# beacon.net
KiCad netlist of a schematic drawn in EAGLE
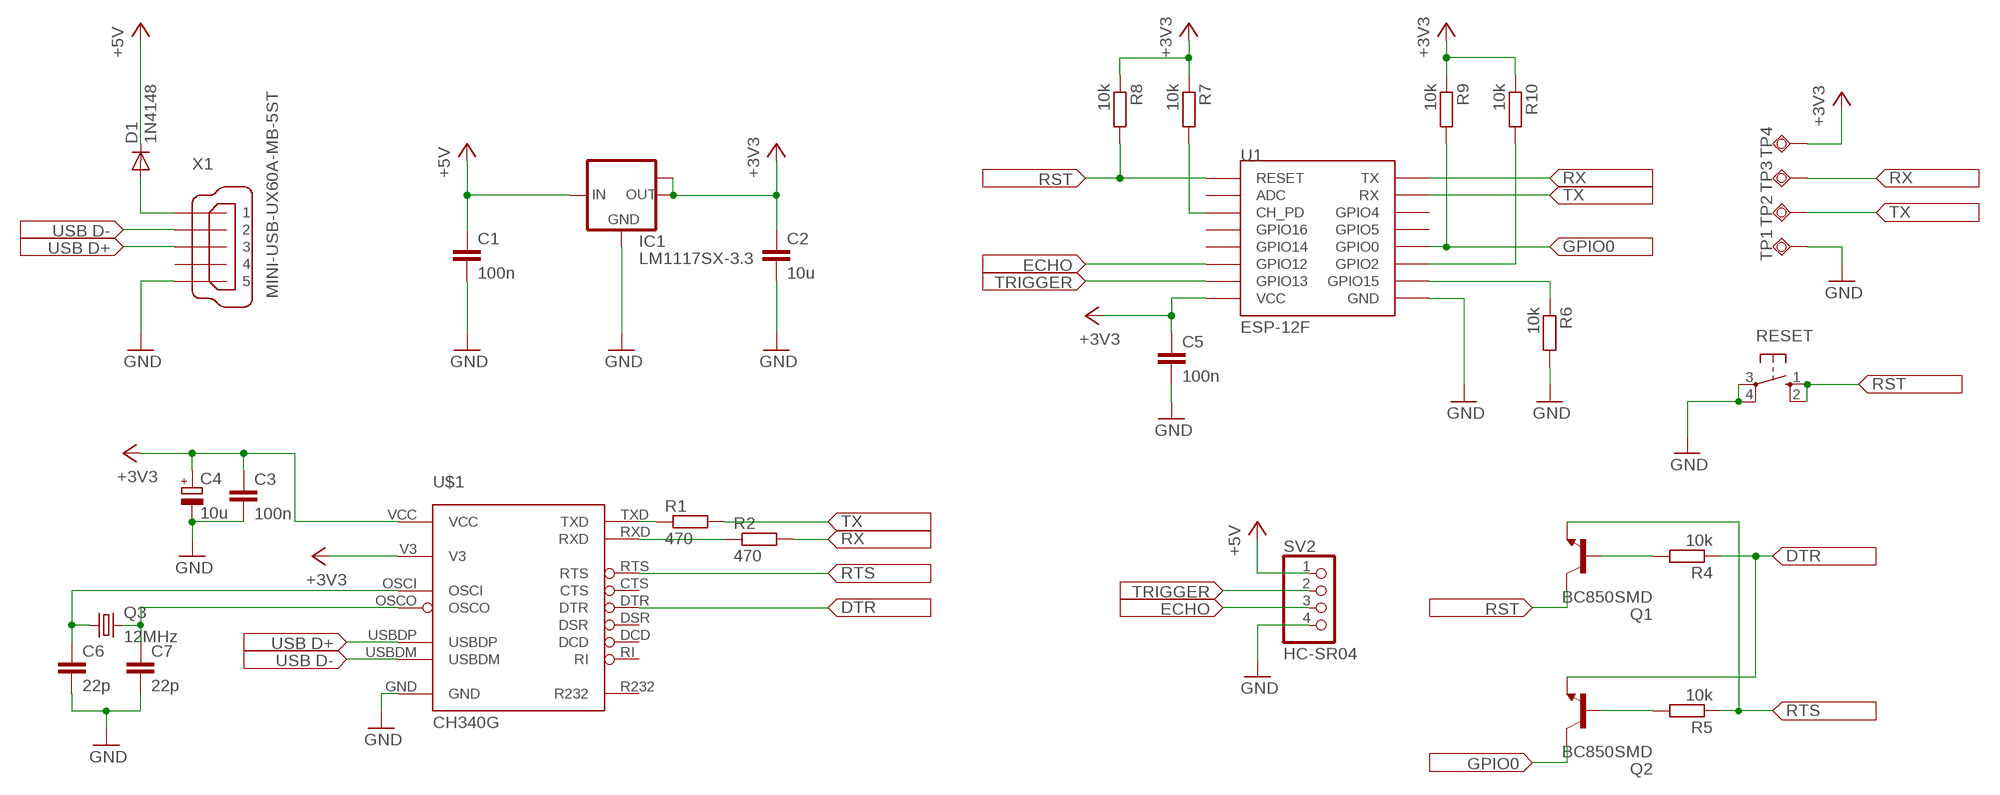
[diagram p0: schematic, sheet 1]

(export (version "E")
  (design (tool "Eeschema 10.0.6"))
  (components
    (comp (ref "C1")
      (value "100n")
      (footprint "eagle-import:C1206K")
      (libsource (lib "eagle-import") (part "C-EUC1206K"))
    )
    (comp (ref "C2")
      (value "10u")
      (footprint "eagle-import:C1206K")
      (libsource (lib "eagle-import") (part "C-EUC1206K"))
    )
    (comp (ref "C3")
      (value "100n")
      (footprint "eagle-import:C1206K")
      (libsource (lib "eagle-import") (part "C-EUC1206K"))
    )
    (comp (ref "C4")
      (value "10u")
      (footprint "eagle-import:175TMP-0810")
      (libsource (lib "eagle-import") (part "CPOL-EU175TMP-0810"))
    )
    (comp (ref "C5")
      (value "100n")
      (footprint "eagle-import:C1206K")
      (libsource (lib "eagle-import") (part "C-EUC1206K"))
    )
    (comp (ref "C6")
      (value "22p")
      (footprint "eagle-import:C1206K")
      (libsource (lib "eagle-import") (part "C-EUC1206K"))
    )
    (comp (ref "C7")
      (value "22p")
      (footprint "eagle-import:C1206K")
      (libsource (lib "eagle-import") (part "C-EUC1206K"))
    )
    (comp (ref "D1")
      (value "1N4148")
      (footprint "eagle-import:SMA")
      (libsource (lib "eagle-import") (part "S1M"))
    )
    (comp (ref "IC1")
      (value "LM1117SX-3.3")
      (footprint "eagle-import:TO263")
      (libsource (lib "eagle-import") (part "LM1117SX-3.3"))
    )
    (comp (ref "Q1")
      (value "BC850SMD")
      (footprint "eagle-import:SOT23-BEC")
      (libsource (lib "eagle-import") (part "BC850SMD"))
    )
    (comp (ref "Q2")
      (value "BC850SMD")
      (footprint "eagle-import:SOT23-BEC")
      (libsource (lib "eagle-import") (part "BC850SMD"))
    )
    (comp (ref "Q3")
      (value "12MHz")
      (footprint "eagle-import:SM49")
      (libsource (lib "eagle-import") (part "CRYSTALSM49"))
    )
    (comp (ref "R1")
      (value "470")
      (footprint "eagle-import:R1206")
      (libsource (lib "eagle-import") (part "R-EU_R1206"))
    )
    (comp (ref "R2")
      (value "470")
      (footprint "eagle-import:R1206")
      (libsource (lib "eagle-import") (part "R-EU_R1206"))
    )
    (comp (ref "R4")
      (value "10k")
      (footprint "eagle-import:R1206")
      (libsource (lib "eagle-import") (part "R-EU_R1206"))
    )
    (comp (ref "R5")
      (value "10k")
      (footprint "eagle-import:R1206")
      (libsource (lib "eagle-import") (part "R-EU_R1206"))
    )
    (comp (ref "R6")
      (value "10k")
      (footprint "eagle-import:R1206")
      (libsource (lib "eagle-import") (part "R-EU_R1206"))
    )
    (comp (ref "R7")
      (value "10k")
      (footprint "eagle-import:R1206")
      (libsource (lib "eagle-import") (part "R-EU_R1206"))
    )
    (comp (ref "R8")
      (value "10k")
      (footprint "eagle-import:R1206")
      (libsource (lib "eagle-import") (part "R-EU_R1206"))
    )
    (comp (ref "R9")
      (value "10k")
      (footprint "eagle-import:R1206")
      (libsource (lib "eagle-import") (part "R-EU_R1206"))
    )
    (comp (ref "R10")
      (value "10k")
      (footprint "eagle-import:R1206")
      (libsource (lib "eagle-import") (part "R-EU_R1206"))
    )
    (comp (ref "RESET")
      (value "10-XX")
      (footprint "eagle-import:B3F-10XX")
      (fields (field (name "MPN") "B3F-1000"))
      (libsource (lib "eagle-import") (part "10-XX"))
    )
    (comp (ref "SV2")
      (value "HC-SR04")
      (footprint "eagle-import:1X04_90")
      (libsource (lib "eagle-import") (part "PINHD-1X4/90"))
    )
    (comp (ref "TP1")
      (value "TPSQTP20SQ")
      (footprint "eagle-import:TP20SQ")
      (libsource (lib "eagle-import") (part "TPSQTP20SQ"))
    )
    (comp (ref "TP2")
      (value "TPSQTP20SQ")
      (footprint "eagle-import:TP20SQ")
      (libsource (lib "eagle-import") (part "TPSQTP20SQ"))
    )
    (comp (ref "TP3")
      (value "TPSQTP20SQ")
      (footprint "eagle-import:TP20SQ")
      (libsource (lib "eagle-import") (part "TPSQTP20SQ"))
    )
    (comp (ref "TP4")
      (value "TPSQTP20SQ")
      (footprint "eagle-import:TP20SQ")
      (libsource (lib "eagle-import") (part "TPSQTP20SQ"))
    )
    (comp (ref "U$1")
      (value "CH340G")
      (footprint "eagle-import:SOP16")
      (libsource (lib "eagle-import") (part "CH340G"))
    )
    (comp (ref "U1")
      (value "ESP-12F")
      (footprint "eagle-import:ESP12-SMD")
      (libsource (lib "eagle-import") (part "ESP12SMD"))
    )
    (comp (ref "X1")
      (value "MINI-USB-UX60A-MB-5ST")
      (footprint "eagle-import:UX60A-MB-5ST")
      (libsource (lib "eagle-import") (part "MINI-USB-UX60A-MB-5ST"))
    )
  )
  (nets
    (net (code "1") (name "+3V3") (class "Default")
      (node (ref "C2") (pin "1") (pinfunction "1_1") (pintype "passive"))
      (node (ref "C3") (pin "1") (pinfunction "1_1") (pintype "passive"))
      (node (ref "C4") (pin "+") (pinfunction "+_+") (pintype "passive"))
      (node (ref "C5") (pin "1") (pinfunction "1_1") (pintype "passive"))
      (node (ref "IC1") (pin "2") (pinfunction "OUT_2") (pintype "passive"))
      (node (ref "IC1") (pin "TAB") (pinfunction "OUT1_TAB") (pintype "passive"))
      (node (ref "R10") (pin "1") (pinfunction "1_1") (pintype "passive"))
      (node (ref "R7") (pin "1") (pinfunction "1_1") (pintype "passive"))
      (node (ref "R8") (pin "1") (pinfunction "1_1") (pintype "passive"))
      (node (ref "R9") (pin "1") (pinfunction "1_1") (pintype "passive"))
      (node (ref "TP4") (pin "TP") (pinfunction "TP_TP") (pintype "input"))
      (node (ref "U$1") (pin "V3") (pinfunction "V3_V3") (pintype "bidirectional"))
      (node (ref "U$1") (pin "VCC") (pinfunction "VCC_VCC") (pintype "bidirectional"))
      (node (ref "U1") (pin "VCC") (pinfunction "VCC_VCC") (pintype "bidirectional"))
    )
    (net (code "2") (name "+5V") (class "Default")
      (node (ref "C1") (pin "1") (pinfunction "1_1") (pintype "passive"))
      (node (ref "D1") (pin "C") (pinfunction "C_C") (pintype "passive"))
      (node (ref "IC1") (pin "3") (pinfunction "IN_3") (pintype "input"))
      (node (ref "SV2") (pin "1") (pinfunction "1_1") (pintype "passive"))
    )
    (net (code "3") (name "/DTR") (class "Default")
      (node (ref "Q2") (pin "E") (pinfunction "E_E") (pintype "passive"))
      (node (ref "R4") (pin "1") (pinfunction "1_1") (pintype "passive"))
      (node (ref "U$1") (pin "DTR") (pinfunction "DTR_DTR") (pintype "bidirectional"))
    )
    (net (code "4") (name "/ECHO") (class "Default")
      (node (ref "SV2") (pin "3") (pinfunction "3_3") (pintype "passive"))
      (node (ref "U1") (pin "GPIO12") (pinfunction "GPIO12_GPIO12") (pintype "bidirectional"))
    )
    (net (code "5") (name "/GPIO0") (class "Default")
      (node (ref "Q2") (pin "C") (pinfunction "C_C") (pintype "passive"))
      (node (ref "R9") (pin "2") (pinfunction "2_2") (pintype "passive"))
      (node (ref "U1") (pin "GPIO0") (pinfunction "GPIO0_GPIO0") (pintype "bidirectional"))
    )
    (net (code "6") (name "/RST") (class "Default")
      (node (ref "Q1") (pin "C") (pinfunction "C_C") (pintype "passive"))
      (node (ref "R8") (pin "2") (pinfunction "2_2") (pintype "passive"))
      (node (ref "RESET") (pin "1") (pinfunction "S_1") (pintype "passive"))
      (node (ref "RESET") (pin "2") (pinfunction "S1_2") (pintype "passive"))
      (node (ref "U1") (pin "RESET") (pinfunction "RESET_RESET") (pintype "bidirectional"))
    )
    (net (code "7") (name "/RTS") (class "Default")
      (node (ref "Q1") (pin "E") (pinfunction "E_E") (pintype "passive"))
      (node (ref "R5") (pin "1") (pinfunction "1_1") (pintype "passive"))
      (node (ref "U$1") (pin "RTS") (pinfunction "RTS_RTS") (pintype "bidirectional"))
    )
    (net (code "8") (name "/RX") (class "Default")
      (node (ref "R2") (pin "2") (pinfunction "2_2") (pintype "passive"))
      (node (ref "TP3") (pin "TP") (pinfunction "TP_TP") (pintype "input"))
      (node (ref "U1") (pin "TXD0") (pinfunction "TX_TXD0") (pintype "bidirectional"))
    )
    (net (code "9") (name "/TRIGGER") (class "Default")
      (node (ref "SV2") (pin "2") (pinfunction "2_2") (pintype "passive"))
      (node (ref "U1") (pin "GPIO13") (pinfunction "GPIO13_GPIO13") (pintype "bidirectional"))
    )
    (net (code "10") (name "/TX") (class "Default")
      (node (ref "R1") (pin "2") (pinfunction "2_2") (pintype "passive"))
      (node (ref "TP2") (pin "TP") (pinfunction "TP_TP") (pintype "input"))
      (node (ref "U1") (pin "RXD0") (pinfunction "RX_RXD0") (pintype "bidirectional"))
    )
    (net (code "11") (name "/USBDM") (class "Default")
      (node (ref "U$1") (pin "USBDM") (pinfunction "USBDM_USBDM") (pintype "bidirectional"))
      (node (ref "X1") (pin "2") (pinfunction "2_2") (pintype "input"))
    )
    (net (code "12") (name "/USBDP") (class "Default")
      (node (ref "U$1") (pin "USBDP") (pinfunction "USBDP_USBDP") (pintype "bidirectional"))
      (node (ref "X1") (pin "3") (pinfunction "3_3") (pintype "input"))
    )
    (net (code "13") (name "GND") (class "Default")
      (node (ref "C1") (pin "2") (pinfunction "2_2") (pintype "passive"))
      (node (ref "C2") (pin "2") (pinfunction "2_2") (pintype "passive"))
      (node (ref "C3") (pin "2") (pinfunction "2_2") (pintype "passive"))
      (node (ref "C4") (pin "-") (pinfunction "-_-") (pintype "passive"))
      (node (ref "C5") (pin "2") (pinfunction "2_2") (pintype "passive"))
      (node (ref "C6") (pin "2") (pinfunction "2_2") (pintype "passive"))
      (node (ref "C7") (pin "2") (pinfunction "2_2") (pintype "passive"))
      (node (ref "IC1") (pin "1") (pinfunction "GND_1") (pintype "input"))
      (node (ref "R6") (pin "2") (pinfunction "2_2") (pintype "passive"))
      (node (ref "RESET") (pin "3") (pinfunction "P_3") (pintype "passive"))
      (node (ref "RESET") (pin "4") (pinfunction "P1_4") (pintype "passive"))
      (node (ref "SV2") (pin "4") (pinfunction "4_4") (pintype "passive"))
      (node (ref "TP1") (pin "TP") (pinfunction "TP_TP") (pintype "input"))
      (node (ref "U$1") (pin "GND") (pinfunction "GND_GND") (pintype "bidirectional"))
      (node (ref "U1") (pin "GND") (pinfunction "GND_GND") (pintype "bidirectional"))
      (node (ref "X1") (pin "5") (pinfunction "5_5") (pintype "input"))
    )
    (net (code "14") (name "Net-(C6-Pad1)") (class "Default")
      (node (ref "C6") (pin "1") (pinfunction "1_1") (pintype "passive"))
      (node (ref "Q3") (pin "1") (pinfunction "1_1") (pintype "passive"))
      (node (ref "U$1") (pin "OSCI") (pinfunction "OSCI_OSCI") (pintype "bidirectional"))
    )
    (net (code "15") (name "Net-(C7-Pad1)") (class "Default")
      (node (ref "C7") (pin "1") (pinfunction "1_1") (pintype "passive"))
      (node (ref "Q3") (pin "2") (pinfunction "2_2") (pintype "passive"))
      (node (ref "U$1") (pin "OSCO") (pinfunction "OSCO_OSCO") (pintype "bidirectional"))
    )
    (net (code "16") (name "Net-(D1-PadA)") (class "Default")
      (node (ref "D1") (pin "A") (pinfunction "A_A") (pintype "passive"))
      (node (ref "X1") (pin "1") (pinfunction "1_1") (pintype "input"))
    )
    (net (code "17") (name "Net-(Q1-PadB)") (class "Default")
      (node (ref "Q1") (pin "B") (pinfunction "B_B") (pintype "passive"))
      (node (ref "R4") (pin "2") (pinfunction "2_2") (pintype "passive"))
    )
    (net (code "18") (name "Net-(Q2-PadB)") (class "Default")
      (node (ref "Q2") (pin "B") (pinfunction "B_B") (pintype "passive"))
      (node (ref "R5") (pin "2") (pinfunction "2_2") (pintype "passive"))
    )
    (net (code "19") (name "Net-(R1-Pad1)") (class "Default")
      (node (ref "R1") (pin "1") (pinfunction "1_1") (pintype "passive"))
      (node (ref "U$1") (pin "TXD") (pinfunction "TXD_TXD") (pintype "bidirectional"))
    )
    (net (code "20") (name "Net-(R2-Pad1)") (class "Default")
      (node (ref "R2") (pin "1") (pinfunction "1_1") (pintype "passive"))
      (node (ref "U$1") (pin "RXD") (pinfunction "RXD_RXD") (pintype "bidirectional"))
    )
    (net (code "21") (name "Net-(R6-Pad1)") (class "Default")
      (node (ref "R6") (pin "1") (pinfunction "1_1") (pintype "passive"))
      (node (ref "U1") (pin "GPIO15") (pinfunction "GPIO15_GPIO15") (pintype "bidirectional"))
    )
    (net (code "22") (name "Net-(R7-Pad2)") (class "Default")
      (node (ref "R7") (pin "2") (pinfunction "2_2") (pintype "passive"))
      (node (ref "U1") (pin "CH_PD") (pinfunction "CH_PD_CH_PD") (pintype "bidirectional"))
    )
    (net (code "23") (name "Net-(R10-Pad2)") (class "Default")
      (node (ref "R10") (pin "2") (pinfunction "2_2") (pintype "passive"))
      (node (ref "U1") (pin "GPIO2") (pinfunction "GPIO2_GPIO2") (pintype "bidirectional"))
    )
    (net (code "24") (name "unconnected-(U$1-PadCTS)") (class "Default")
      (node (ref "U$1") (pin "CTS") (pinfunction "CTS_CTS") (pintype "bidirectional"))
    )
    (net (code "25") (name "unconnected-(U$1-PadDCD)") (class "Default")
      (node (ref "U$1") (pin "DCD") (pinfunction "DCD_DCD") (pintype "bidirectional"))
    )
    (net (code "26") (name "unconnected-(U$1-PadDSR)") (class "Default")
      (node (ref "U$1") (pin "DSR") (pinfunction "DSR_DSR") (pintype "bidirectional"))
    )
    (net (code "27") (name "unconnected-(U$1-PadR232)") (class "Default")
      (node (ref "U$1") (pin "R232") (pinfunction "R232_R232") (pintype "bidirectional"))
    )
    (net (code "28") (name "unconnected-(U$1-PadRI)") (class "Default")
      (node (ref "U$1") (pin "RI") (pinfunction "RI_RI") (pintype "bidirectional"))
    )
    (net (code "29") (name "unconnected-(U1-PadADC)") (class "Default")
      (node (ref "U1") (pin "ADC") (pinfunction "ADC_ADC") (pintype "bidirectional"))
    )
    (net (code "30") (name "unconnected-(U1-PadGPIO4)") (class "Default")
      (node (ref "U1") (pin "GPIO4") (pinfunction "GPIO4_GPIO4") (pintype "bidirectional"))
    )
    (net (code "31") (name "unconnected-(U1-PadGPIO5)") (class "Default")
      (node (ref "U1") (pin "GPIO5") (pinfunction "GPIO5_GPIO5") (pintype "bidirectional"))
    )
    (net (code "32") (name "unconnected-(U1-PadGPIO14)") (class "Default")
      (node (ref "U1") (pin "GPIO14") (pinfunction "GPIO14_GPIO14") (pintype "bidirectional"))
    )
    (net (code "33") (name "unconnected-(U1-PadGPIO16)") (class "Default")
      (node (ref "U1") (pin "GPIO16") (pinfunction "GPIO16_GPIO16") (pintype "bidirectional"))
    )
    (net (code "34") (name "unconnected-(X1-Pad4)") (class "Default")
      (node (ref "X1") (pin "4") (pinfunction "4_4") (pintype "input"))
    )
  )
)
